# cam_cross_link.net
KiCad netlist of a schematic drawn in Altium Designer
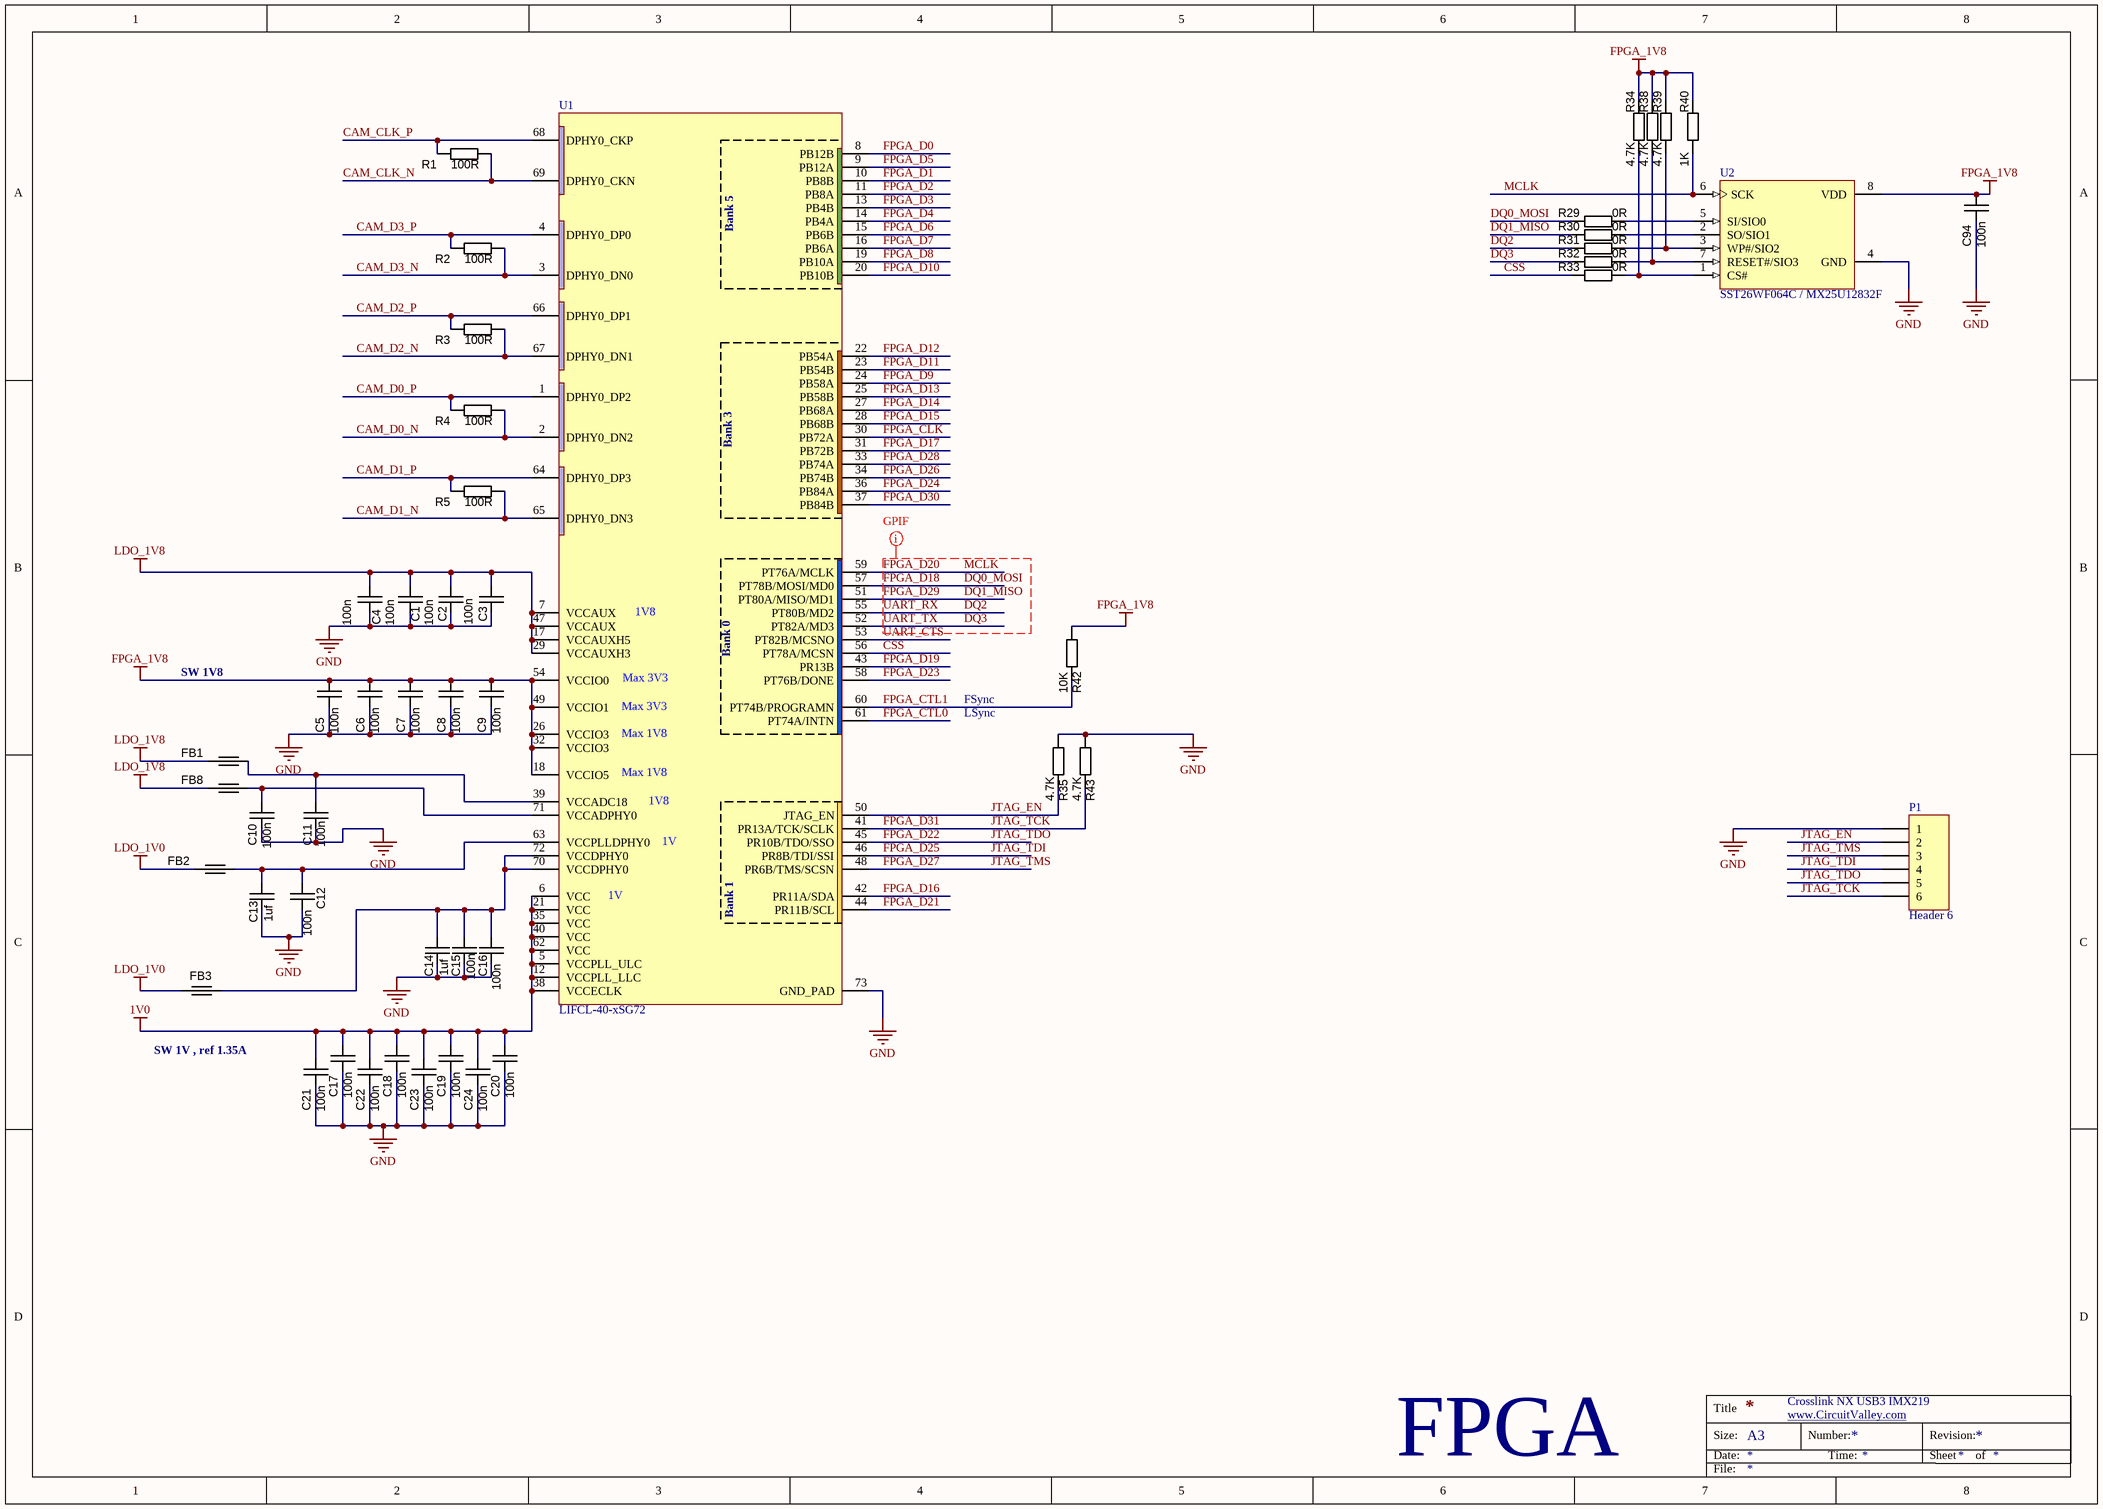
[diagram p0: cam_cross_link.SchDoc]

(export (version "E")
  (design (tool "Eeschema 10.0.6"))
  (components
    (comp (ref "C1")
      (value "100n")
      (footprint "CAPC1608N")
      (description "Capacitor SMD Cer 10pF 5% 50V NP0 0603")
      (fields (field (name "TOLERANCE") "±5%") (field (name "PART") "C0603X104K5RAC"))
      (libsource (lib "PBL - Capacitors") (part "CAPC_10p_0603_NP0_1%_50V"))
    )
    (comp (ref "C2")
      (value "100n")
      (footprint "CAPC1608N")
      (description "Capacitor SMD Cer 10pF 5% 50V NP0 0603")
      (fields (field (name "TOLERANCE") "±5%") (field (name "PART") "C0603X104K5RAC"))
      (libsource (lib "PBL - Capacitors") (part "CAPC_10p_0603_NP0_1%_50V"))
    )
    (comp (ref "C3")
      (value "100n")
      (footprint "CAPC1608N")
      (description "Capacitor SMD Cer 10pF 5% 50V NP0 0603")
      (fields (field (name "TOLERANCE") "±5%") (field (name "PART") "C0603X104K5RAC"))
      (libsource (lib "PBL - Capacitors") (part "CAPC_10p_0603_NP0_1%_50V"))
    )
    (comp (ref "C4")
      (value "100n")
      (footprint "CAPC1608N")
      (description "Capacitor SMD Cer 10pF 5% 50V NP0 0603")
      (fields (field (name "TOLERANCE") "±5%") (field (name "PART") "C0603X104K5RAC"))
      (libsource (lib "PBL - Capacitors") (part "CAPC_10p_0603_NP0_1%_50V"))
    )
    (comp (ref "C5")
      (value "100n")
      (footprint "CAPC1608N")
      (description "Capacitor SMD Cer 10pF 5% 50V NP0 0603")
      (fields (field (name "TOLERANCE") "±5%") (field (name "PART") "C0603X104K5RAC"))
      (libsource (lib "PBL - Capacitors") (part "CAPC_10p_0603_NP0_1%_50V"))
    )
    (comp (ref "C6")
      (value "100n")
      (footprint "CAPC1608N")
      (description "Capacitor SMD Cer 10pF 5% 50V NP0 0603")
      (fields (field (name "TOLERANCE") "±5%") (field (name "PART") "C0603X104K5RAC"))
      (libsource (lib "PBL - Capacitors") (part "CAPC_10p_0603_NP0_1%_50V"))
    )
    (comp (ref "C7")
      (value "100n")
      (footprint "CAPC1608N")
      (description "Capacitor SMD Cer 10pF 5% 50V NP0 0603")
      (fields (field (name "TOLERANCE") "±5%") (field (name "PART") "C0603X104K5RAC"))
      (libsource (lib "PBL - Capacitors") (part "CAPC_10p_0603_NP0_1%_50V"))
    )
    (comp (ref "C8")
      (value "100n")
      (footprint "CAPC1608N")
      (description "Capacitor SMD Cer 10pF 5% 50V NP0 0603")
      (fields (field (name "TOLERANCE") "±5%") (field (name "PART") "C0603X104K5RAC"))
      (libsource (lib "PBL - Capacitors") (part "CAPC_10p_0603_NP0_1%_50V"))
    )
    (comp (ref "C9")
      (value "100n")
      (footprint "CAPC1608N")
      (description "Capacitor SMD Cer 10pF 5% 50V NP0 0603")
      (fields (field (name "TOLERANCE") "±5%") (field (name "PART") "C0603X104K5RAC"))
      (libsource (lib "PBL - Capacitors") (part "CAPC_10p_0603_NP0_1%_50V"))
    )
    (comp (ref "C10")
      (value "100n")
      (footprint "CAPC1608N")
      (description "Capacitor SMD Cer 10pF 5% 50V NP0 0603")
      (fields (field (name "TOLERANCE") "±5%") (field (name "PART") "C0603X104K5RAC"))
      (libsource (lib "PBL - Capacitors") (part "CAPC_10p_0603_NP0_1%_50V"))
    )
    (comp (ref "C11")
      (value "100n")
      (footprint "CAPC1608N")
      (description "Capacitor SMD Cer 10pF 5% 50V NP0 0603")
      (fields (field (name "TOLERANCE") "±5%") (field (name "PART") "C0603X104K5RAC"))
      (libsource (lib "PBL - Capacitors") (part "CAPC_10p_0603_NP0_1%_50V"))
    )
    (comp (ref "C12")
      (value "100n")
      (footprint "CAPC1608N")
      (description "Capacitor SMD Cer 10pF 5% 50V NP0 0603")
      (fields (field (name "TOLERANCE") "±5%") (field (name "PART") "C0603X104K5RAC"))
      (libsource (lib "PBL - Capacitors") (part "CAPC_10p_0603_NP0_1%_50V"))
    )
    (comp (ref "C13")
      (value "1uf")
      (footprint "CAPC1608N")
      (description "Capacitor SMD Cer 10pF 5% 50V NP0 0603")
      (fields (field (name "TOLERANCE") "±5%") (field (name "PART") "C0603X104K5RAC"))
      (libsource (lib "PBL - Capacitors") (part "CAPC_10p_0603_NP0_1%_50V"))
    )
    (comp (ref "C14")
      (value "1uf")
      (footprint "CAPC1608N")
      (description "Capacitor SMD Cer 10pF 5% 50V NP0 0603")
      (fields (field (name "TOLERANCE") "±5%") (field (name "PART") "C0603X104K5RAC"))
      (libsource (lib "PBL - Capacitors") (part "CAPC_10p_0603_NP0_1%_50V"))
    )
    (comp (ref "C15")
      (value "100n")
      (footprint "CAPC1608N")
      (description "Capacitor SMD Cer 10pF 5% 50V NP0 0603")
      (fields (field (name "TOLERANCE") "±5%") (field (name "PART") "C0603X104K5RAC"))
      (libsource (lib "PBL - Capacitors") (part "CAPC_10p_0603_NP0_1%_50V"))
    )
    (comp (ref "C16")
      (value "100n")
      (footprint "CAPC1608N")
      (description "Capacitor SMD Cer 10pF 5% 50V NP0 0603")
      (fields (field (name "TOLERANCE") "±5%") (field (name "PART") "C0603X104K5RAC"))
      (libsource (lib "PBL - Capacitors") (part "CAPC_10p_0603_NP0_1%_50V"))
    )
    (comp (ref "C17")
      (value "100n")
      (footprint "CAPC1608N")
      (description "Capacitor SMD Cer 10pF 5% 50V NP0 0603")
      (fields (field (name "TOLERANCE") "±5%") (field (name "PART") "C0603X104K5RAC"))
      (libsource (lib "PBL - Capacitors") (part "CAPC_10p_0603_NP0_1%_50V"))
    )
    (comp (ref "C18")
      (value "100n")
      (footprint "CAPC1608N")
      (description "Capacitor SMD Cer 10pF 5% 50V NP0 0603")
      (fields (field (name "TOLERANCE") "±5%") (field (name "PART") "C0603X104K5RAC"))
      (libsource (lib "PBL - Capacitors") (part "CAPC_10p_0603_NP0_1%_50V"))
    )
    (comp (ref "C19")
      (value "100n")
      (footprint "CAPC1608N")
      (description "Capacitor SMD Cer 10pF 5% 50V NP0 0603")
      (fields (field (name "TOLERANCE") "±5%") (field (name "PART") "C0603X104K5RAC"))
      (libsource (lib "PBL - Capacitors") (part "CAPC_10p_0603_NP0_1%_50V"))
    )
    (comp (ref "C20")
      (value "100n")
      (footprint "CAPC1608N")
      (description "Capacitor SMD Cer 10pF 5% 50V NP0 0603")
      (fields (field (name "TOLERANCE") "±5%") (field (name "PART") "C0603X104K5RAC"))
      (libsource (lib "PBL - Capacitors") (part "CAPC_10p_0603_NP0_1%_50V"))
    )
    (comp (ref "C21")
      (value "100n")
      (footprint "CAPC1608N")
      (description "Capacitor SMD Cer 10pF 5% 50V NP0 0603")
      (fields (field (name "TOLERANCE") "±5%") (field (name "PART") "C0603X104K5RAC"))
      (libsource (lib "PBL - Capacitors") (part "CAPC_10p_0603_NP0_1%_50V"))
    )
    (comp (ref "C22")
      (value "100n")
      (footprint "CAPC1608N")
      (description "Capacitor SMD Cer 10pF 5% 50V NP0 0603")
      (fields (field (name "TOLERANCE") "±5%") (field (name "PART") "C0603X104K5RAC"))
      (libsource (lib "PBL - Capacitors") (part "CAPC_10p_0603_NP0_1%_50V"))
    )
    (comp (ref "C23")
      (value "100n")
      (footprint "CAPC1608N")
      (description "Capacitor SMD Cer 10pF 5% 50V NP0 0603")
      (fields (field (name "TOLERANCE") "±5%") (field (name "PART") "C0603X104K5RAC"))
      (libsource (lib "PBL - Capacitors") (part "CAPC_10p_0603_NP0_1%_50V"))
    )
    (comp (ref "C24")
      (value "100n")
      (footprint "CAPC1608N")
      (description "Capacitor SMD Cer 10pF 5% 50V NP0 0603")
      (fields (field (name "TOLERANCE") "±5%") (field (name "PART") "C0603X104K5RAC"))
      (libsource (lib "PBL - Capacitors") (part "CAPC_10p_0603_NP0_1%_50V"))
    )
    (comp (ref "C94")
      (value "100n")
      (footprint "CAPC1608N")
      (description "Capacitor SMD Cer 10pF 5% 50V NP0 0603")
      (fields (field (name "TOLERANCE") "±5%") (field (name "PART") "C0603X104K5RAC"))
      (libsource (lib "PBL - Capacitors") (part "CAPC_10p_0603_NP0_1%_50V"))
    )
    (comp (ref "FB1")
      (value "~")
      (footprint "FBC2012N")
      (description "Ferrite bead 2.2K Ohm at 100 MHz 200mA 0805 SMD")
      (libsource (lib "PBL - Inductors") (part "FERRITE_0805"))
    )
    (comp (ref "FB2")
      (value "~")
      (footprint "FBC2012N")
      (description "Ferrite bead 2.2K Ohm at 100 MHz 200mA 0805 SMD")
      (libsource (lib "PBL - Inductors") (part "FERRITE_0805"))
    )
    (comp (ref "FB3")
      (value "~")
      (footprint "FBC2012N")
      (description "Ferrite bead 2.2K Ohm at 100 MHz 200mA 0805 SMD")
      (libsource (lib "PBL - Inductors") (part "FERRITE_0805"))
    )
    (comp (ref "FB8")
      (value "~")
      (footprint "FBC2012N")
      (description "Ferrite bead 2.2K Ohm at 100 MHz 200mA 0805 SMD")
      (libsource (lib "PBL - Inductors") (part "FERRITE_0805"))
    )
    (comp (ref "P1")
      (value "Header 6")
      (footprint "SMD_Solder_points_1.27")
      (description "Header, 6-Pin")
      (fields (field (name "PUBLISHER") "Altium Limited"))
      (libsource (lib "Miscellaneous Connectors") (part "Header 6"))
    )
    (comp (ref "R1")
      (value "100R")
      (footprint "RESC1005N")
      (description "Resistor SMD chip 1M Ohm 0.063W 5% 0402")
      (fields (field (name "TOLERANCE") "±5%") (field (name "Comment") "Thick Film"))
      (libsource (lib "PBL - Resistors") (part "RES_1M_0402_5%"))
    )
    (comp (ref "R2")
      (value "100R")
      (footprint "RESC1005N")
      (description "Resistor SMD chip 1M Ohm 0.063W 5% 0402")
      (fields (field (name "TOLERANCE") "±5%") (field (name "Comment") "Thick Film"))
      (libsource (lib "PBL - Resistors") (part "RES_1M_0402_5%"))
    )
    (comp (ref "R3")
      (value "100R")
      (footprint "RESC1005N")
      (description "Resistor SMD chip 1M Ohm 0.063W 5% 0402")
      (fields (field (name "TOLERANCE") "±5%") (field (name "Comment") "Thick Film"))
      (libsource (lib "PBL - Resistors") (part "RES_1M_0402_5%"))
    )
    (comp (ref "R4")
      (value "100R")
      (footprint "RESC1005N")
      (description "Resistor SMD chip 1M Ohm 0.063W 5% 0402")
      (fields (field (name "TOLERANCE") "±5%") (field (name "Comment") "Thick Film"))
      (libsource (lib "PBL - Resistors") (part "RES_1M_0402_5%"))
    )
    (comp (ref "R5")
      (value "100R")
      (footprint "RESC1005N")
      (description "Resistor SMD chip 1M Ohm 0.063W 5% 0402")
      (fields (field (name "TOLERANCE") "±5%") (field (name "Comment") "Thick Film"))
      (libsource (lib "PBL - Resistors") (part "RES_1M_0402_5%"))
    )
    (comp (ref "R29")
      (value "0R")
      (footprint "RESC1608N_ZERO")
      (description "Resistor SMD chip 0.0 Ohm 0.1W 0603")
      (fields (field (name "TOLERANCE") "±5%") (field (name "Comment") "Thick Film"))
      (libsource (lib "") (part "RES_0R_0603_1"))
    )
    (comp (ref "R30")
      (value "0R")
      (footprint "RESC1608N_ZERO")
      (description "Resistor SMD chip 0.0 Ohm 0.1W 0603")
      (fields (field (name "TOLERANCE") "±5%") (field (name "Comment") "Thick Film"))
      (libsource (lib "") (part "RES_0R_0603_1"))
    )
    (comp (ref "R31")
      (value "0R")
      (footprint "RESC1608N_ZERO")
      (description "Resistor SMD chip 0.0 Ohm 0.1W 0603")
      (fields (field (name "TOLERANCE") "±5%") (field (name "Comment") "Thick Film"))
      (libsource (lib "") (part "RES_0R_0603_1"))
    )
    (comp (ref "R32")
      (value "0R")
      (footprint "RESC1608N_ZERO")
      (description "Resistor SMD chip 0.0 Ohm 0.1W 0603")
      (fields (field (name "TOLERANCE") "±5%") (field (name "Comment") "Thick Film"))
      (libsource (lib "") (part "RES_0R_0603_1"))
    )
    (comp (ref "R33")
      (value "0R")
      (footprint "RESC1608N_ZERO")
      (description "Resistor SMD chip 0.0 Ohm 0.1W 0603")
      (fields (field (name "TOLERANCE") "±5%") (field (name "Comment") "Thick Film"))
      (libsource (lib "") (part "RES_0R_0603_1"))
    )
    (comp (ref "R34")
      (value "4.7K")
      (footprint "RESC1608N_ZERO")
      (description "Resistor SMD chip 0.0 Ohm 0.1W 0603")
      (fields (field (name "TOLERANCE") "±5%") (field (name "Comment") "Thick Film"))
      (libsource (lib "PBL - Resistors") (part "RES_0R_0603"))
    )
    (comp (ref "R35")
      (value "4.7K")
      (footprint "RESC1608N_ZERO")
      (description "Resistor SMD chip 0.0 Ohm 0.1W 0603")
      (fields (field (name "TOLERANCE") "±5%") (field (name "Comment") "Thick Film"))
      (libsource (lib "PBL - Resistors") (part "RES_0R_0603"))
    )
    (comp (ref "R38")
      (value "4.7K")
      (footprint "RESC1608N_ZERO")
      (description "Resistor SMD chip 0.0 Ohm 0.1W 0603")
      (fields (field (name "TOLERANCE") "±5%") (field (name "Comment") "Thick Film"))
      (libsource (lib "PBL - Resistors") (part "RES_0R_0603"))
    )
    (comp (ref "R39")
      (value "4.7K")
      (footprint "RESC1608N_ZERO")
      (description "Resistor SMD chip 0.0 Ohm 0.1W 0603")
      (fields (field (name "TOLERANCE") "±5%") (field (name "Comment") "Thick Film"))
      (libsource (lib "PBL - Resistors") (part "RES_0R_0603"))
    )
    (comp (ref "R40")
      (value "1K")
      (footprint "RESC1608N_ZERO")
      (description "Resistor SMD chip 0.0 Ohm 0.1W 0603")
      (fields (field (name "TOLERANCE") "±5%") (field (name "Comment") "Thick Film"))
      (libsource (lib "PBL - Resistors") (part "RES_0R_0603"))
    )
    (comp (ref "R42")
      (value "10K")
      (footprint "RESC1608N_ZERO")
      (description "Resistor SMD chip 0.0 Ohm 0.1W 0603")
      (fields (field (name "TOLERANCE") "±5%") (field (name "Comment") "Thick Film"))
      (libsource (lib "PBL - Resistors") (part "RES_0R_0603"))
    )
    (comp (ref "R43")
      (value "4.7K")
      (footprint "RESC1608N_ZERO")
      (description "Resistor SMD chip 0.0 Ohm 0.1W 0603")
      (fields (field (name "TOLERANCE") "±5%") (field (name "Comment") "Thick Film"))
      (libsource (lib "PBL - Resistors") (part "RES_0R_0603"))
    )
    (comp (ref "U1")
      (value "LIFCL-40-xSG72")
      (footprint "QFN72_NX")
      (description "QFN 72 LIFCL")
      (libsource (lib "lattice_fpga") (part "LIFCL-40-xSG72"))
    )
    (comp (ref "U2")
      (value "SST26WF064C / MX25U12832F")
      (footprint "SOP8")
      (description "Flash 128Mbit for Lattice FPGA")
      (libsource (lib "cvlib") (part "MX25L12833F"))
    )
  )
  (nets
    (net (code "1") (name "/CAM_CLK_N") (class "Default")
      (node (ref "R1") (pin "1") (pinfunction "1_1") (pintype "passive"))
      (node (ref "U1") (pin "69") (pinfunction "DPHY0_CKN_69") (pintype "passive"))
    )
    (net (code "2") (name "/CAM_CLK_P") (class "Default")
      (node (ref "R1") (pin "2") (pinfunction "2_2") (pintype "passive"))
      (node (ref "U1") (pin "68") (pinfunction "DPHY0_CKP_68") (pintype "passive"))
    )
    (net (code "3") (name "/CAM_D0_N") (class "Default")
      (node (ref "R4") (pin "1") (pinfunction "1_1") (pintype "passive"))
      (node (ref "U1") (pin "2") (pinfunction "DPHY0_DN2_2") (pintype "passive"))
    )
    (net (code "4") (name "/CAM_D0_P") (class "Default")
      (node (ref "R4") (pin "2") (pinfunction "2_2") (pintype "passive"))
      (node (ref "U1") (pin "1") (pinfunction "DPHY0_DP2_1") (pintype "passive"))
    )
    (net (code "5") (name "/CAM_D1_N") (class "Default")
      (node (ref "R5") (pin "1") (pinfunction "1_1") (pintype "passive"))
      (node (ref "U1") (pin "65") (pinfunction "DPHY0_DN3_65") (pintype "passive"))
    )
    (net (code "6") (name "/CAM_D1_P") (class "Default")
      (node (ref "R5") (pin "2") (pinfunction "2_2") (pintype "passive"))
      (node (ref "U1") (pin "64") (pinfunction "DPHY0_DP3_64") (pintype "passive"))
    )
    (net (code "7") (name "/CAM_D2_N") (class "Default")
      (node (ref "R3") (pin "1") (pinfunction "1_1") (pintype "passive"))
      (node (ref "U1") (pin "67") (pinfunction "DPHY0_DN1_67") (pintype "passive"))
    )
    (net (code "8") (name "/CAM_D2_P") (class "Default")
      (node (ref "R3") (pin "2") (pinfunction "2_2") (pintype "passive"))
      (node (ref "U1") (pin "66") (pinfunction "DPHY0_DP1_66") (pintype "passive"))
    )
    (net (code "9") (name "/CAM_D3_N") (class "Default")
      (node (ref "R2") (pin "1") (pinfunction "1_1") (pintype "passive"))
      (node (ref "U1") (pin "3") (pinfunction "DPHY0_DN0_3") (pintype "passive"))
    )
    (net (code "10") (name "/CAM_D3_P") (class "Default")
      (node (ref "R2") (pin "2") (pinfunction "2_2") (pintype "passive"))
      (node (ref "U1") (pin "4") (pinfunction "DPHY0_DP0_4") (pintype "passive"))
    )
    (net (code "11") (name "/CSS") (class "Default")
      (node (ref "R33") (pin "2") (pinfunction "2_2") (pintype "passive"))
      (node (ref "U1") (pin "56") (pinfunction "PT78A/MCSN_56") (pintype "passive"))
    )
    (net (code "12") (name "/DQ0_MOSI") (class "Default")
      (node (ref "R29") (pin "2") (pinfunction "2_2") (pintype "passive"))
      (node (ref "U1") (pin "57") (pinfunction "PT78B/MOSI/MD0_57") (pintype "passive"))
    )
    (net (code "13") (name "/DQ1_MISO") (class "Default")
      (node (ref "R30") (pin "2") (pinfunction "2_2") (pintype "passive"))
      (node (ref "U1") (pin "51") (pinfunction "PT80A/MISO/MD1_51") (pintype "passive"))
    )
    (net (code "14") (name "/DQ2") (class "Default")
      (node (ref "R31") (pin "2") (pinfunction "2_2") (pintype "passive"))
      (node (ref "U1") (pin "55") (pinfunction "PT80B/MD2_55") (pintype "passive"))
    )
    (net (code "15") (name "/DQ3") (class "Default")
      (node (ref "R32") (pin "2") (pinfunction "2_2") (pintype "passive"))
      (node (ref "U1") (pin "52") (pinfunction "PT82A/MD3_52") (pintype "passive"))
    )
    (net (code "16") (name "/FPGA_CLK") (class "Default")
      (node (ref "U1") (pin "30") (pinfunction "PB72A_30") (pintype "passive"))
    )
    (net (code "17") (name "/FPGA_CTL0") (class "Default")
      (node (ref "U1") (pin "61") (pinfunction "PT74A/INTN_61") (pintype "passive"))
    )
    (net (code "18") (name "/FPGA_CTL1") (class "Default")
      (node (ref "R42") (pin "2") (pinfunction "2_2") (pintype "passive"))
      (node (ref "U1") (pin "60") (pinfunction "PT74B/PROGRAMN_60") (pintype "passive"))
    )
    (net (code "19") (name "/FPGA_D0") (class "Default")
      (node (ref "U1") (pin "8") (pinfunction "PB12B_8") (pintype "passive"))
    )
    (net (code "20") (name "/FPGA_D1") (class "Default")
      (node (ref "U1") (pin "10") (pinfunction "PB8B_10") (pintype "passive"))
    )
    (net (code "21") (name "/FPGA_D2") (class "Default")
      (node (ref "U1") (pin "11") (pinfunction "PB8A_11") (pintype "passive"))
    )
    (net (code "22") (name "/FPGA_D3") (class "Default")
      (node (ref "U1") (pin "13") (pinfunction "PB4B_13") (pintype "passive"))
    )
    (net (code "23") (name "/FPGA_D4") (class "Default")
      (node (ref "U1") (pin "14") (pinfunction "PB4A_14") (pintype "passive"))
    )
    (net (code "24") (name "/FPGA_D5") (class "Default")
      (node (ref "U1") (pin "9") (pinfunction "PB12A_9") (pintype "passive"))
    )
    (net (code "25") (name "/FPGA_D6") (class "Default")
      (node (ref "U1") (pin "15") (pinfunction "PB6B_15") (pintype "passive"))
    )
    (net (code "26") (name "/FPGA_D7") (class "Default")
      (node (ref "U1") (pin "16") (pinfunction "PB6A_16") (pintype "passive"))
    )
    (net (code "27") (name "/FPGA_D8") (class "Default")
      (node (ref "U1") (pin "19") (pinfunction "PB10A_19") (pintype "passive"))
    )
    (net (code "28") (name "/FPGA_D9") (class "Default")
      (node (ref "U1") (pin "24") (pinfunction "PB58A_24") (pintype "passive"))
    )
    (net (code "29") (name "/FPGA_D10") (class "Default")
      (node (ref "U1") (pin "20") (pinfunction "PB10B_20") (pintype "passive"))
    )
    (net (code "30") (name "/FPGA_D11") (class "Default")
      (node (ref "U1") (pin "23") (pinfunction "PB54B_23") (pintype "passive"))
    )
    (net (code "31") (name "/FPGA_D12") (class "Default")
      (node (ref "U1") (pin "22") (pinfunction "PB54A_22") (pintype "passive"))
    )
    (net (code "32") (name "/FPGA_D13") (class "Default")
      (node (ref "U1") (pin "25") (pinfunction "PB58B_25") (pintype "passive"))
    )
    (net (code "33") (name "/FPGA_D14") (class "Default")
      (node (ref "U1") (pin "27") (pinfunction "PB68A_27") (pintype "passive"))
    )
    (net (code "34") (name "/FPGA_D15") (class "Default")
      (node (ref "U1") (pin "28") (pinfunction "PB68B_28") (pintype "passive"))
    )
    (net (code "35") (name "/FPGA_D16") (class "Default")
      (node (ref "U1") (pin "42") (pinfunction "PR11A/SDA_42") (pintype "passive"))
    )
    (net (code "36") (name "/FPGA_D17") (class "Default")
      (node (ref "U1") (pin "31") (pinfunction "PB72B_31") (pintype "passive"))
    )
    (net (code "37") (name "/FPGA_D19") (class "Default")
      (node (ref "U1") (pin "43") (pinfunction "PR13B_43") (pintype "passive"))
    )
    (net (code "38") (name "/FPGA_D20") (class "Default")
      (node (ref "R40") (pin "2") (pinfunction "2_2") (pintype "passive"))
      (node (ref "U1") (pin "59") (pinfunction "PT76A/MCLK_59") (pintype "passive"))
      (node (ref "U2") (pin "6") (pinfunction "SCK_6") (pintype "input"))
    )
    (net (code "39") (name "/FPGA_D21") (class "Default")
      (node (ref "U1") (pin "44") (pinfunction "PR11B/SCL_44") (pintype "passive"))
    )
    (net (code "40") (name "/FPGA_D22") (class "Default")
      (node (ref "P1") (pin "5") (pinfunction "5_5") (pintype "passive"))
      (node (ref "U1") (pin "45") (pinfunction "PR10B/TDO/SSO_45") (pintype "passive"))
    )
    (net (code "41") (name "/FPGA_D23") (class "Default")
      (node (ref "U1") (pin "58") (pinfunction "PT76B/DONE_58") (pintype "passive"))
    )
    (net (code "42") (name "/FPGA_D24") (class "Default")
      (node (ref "U1") (pin "36") (pinfunction "PB84A_36") (pintype "passive"))
    )
    (net (code "43") (name "/FPGA_D25") (class "Default")
      (node (ref "P1") (pin "4") (pinfunction "4_4") (pintype "passive"))
      (node (ref "U1") (pin "46") (pinfunction "PR8B/TDI/SSI_46") (pintype "passive"))
    )
    (net (code "44") (name "/FPGA_D26") (class "Default")
      (node (ref "U1") (pin "34") (pinfunction "PB74B_34") (pintype "passive"))
    )
    (net (code "45") (name "/FPGA_D27") (class "Default")
      (node (ref "P1") (pin "3") (pinfunction "3_3") (pintype "passive"))
      (node (ref "U1") (pin "48") (pinfunction "PR6B/TMS/SCSN_48") (pintype "passive"))
    )
    (net (code "46") (name "/FPGA_D28") (class "Default")
      (node (ref "U1") (pin "33") (pinfunction "PB74A_33") (pintype "passive"))
    )
    (net (code "47") (name "/FPGA_D30") (class "Default")
      (node (ref "U1") (pin "37") (pinfunction "PB84B_37") (pintype "passive"))
    )
    (net (code "48") (name "/FPGA_D31") (class "Default")
      (node (ref "P1") (pin "6") (pinfunction "6_6") (pintype "passive"))
      (node (ref "R43") (pin "2") (pinfunction "2_2") (pintype "passive"))
      (node (ref "U1") (pin "41") (pinfunction "PR13A/TCK/SCLK_41") (pintype "passive"))
    )
    (net (code "49") (name "/JTAG_EN") (class "Default")
      (node (ref "P1") (pin "2") (pinfunction "2_2") (pintype "passive"))
      (node (ref "R35") (pin "2") (pinfunction "2_2") (pintype "passive"))
      (node (ref "U1") (pin "50") (pinfunction "JTAG_EN_50") (pintype "passive"))
    )
    (net (code "50") (name "/UART_CTS") (class "Default")
      (node (ref "U1") (pin "53") (pinfunction "PT82B/MCSNO_53") (pintype "passive"))
    )
    (net (code "51") (name "1V0") (class "Default")
      (node (ref "C17") (pin "2") (pintype "passive"))
      (node (ref "C18") (pin "2") (pintype "passive"))
      (node (ref "C19") (pin "2") (pintype "passive"))
      (node (ref "C20") (pin "2") (pintype "passive"))
      (node (ref "C21") (pin "2") (pintype "passive"))
      (node (ref "C22") (pin "2") (pintype "passive"))
      (node (ref "C23") (pin "2") (pintype "passive"))
      (node (ref "C24") (pin "2") (pintype "passive"))
      (node (ref "U1") (pin "12") (pinfunction "VCCPLL_LLC_12") (pintype "power_in"))
      (node (ref "U1") (pin "21") (pinfunction "VCC_21") (pintype "power_in"))
      (node (ref "U1") (pin "35") (pinfunction "VCC_35") (pintype "power_in"))
      (node (ref "U1") (pin "38") (pinfunction "VCCECLK_38") (pintype "power_in"))
      (node (ref "U1") (pin "40") (pinfunction "VCC_40") (pintype "power_in"))
      (node (ref "U1") (pin "5") (pinfunction "VCCPLL_ULC_5") (pintype "power_in"))
      (node (ref "U1") (pin "6") (pinfunction "VCC_6") (pintype "power_in"))
      (node (ref "U1") (pin "62") (pinfunction "VCC_62") (pintype "power_in"))
    )
    (net (code "52") (name "FPGA_1V8") (class "Default")
      (node (ref "C5") (pin "2") (pintype "passive"))
      (node (ref "C6") (pin "2") (pintype "passive"))
      (node (ref "C7") (pin "2") (pintype "passive"))
      (node (ref "C8") (pin "2") (pintype "passive"))
      (node (ref "C9") (pin "2") (pintype "passive"))
      (node (ref "C94") (pin "2") (pintype "passive"))
      (node (ref "R34") (pin "1") (pinfunction "1_1") (pintype "passive"))
      (node (ref "R38") (pin "1") (pinfunction "1_1") (pintype "passive"))
      (node (ref "R39") (pin "1") (pinfunction "1_1") (pintype "passive"))
      (node (ref "R40") (pin "1") (pinfunction "1_1") (pintype "passive"))
      (node (ref "R42") (pin "1") (pinfunction "1_1") (pintype "passive"))
      (node (ref "U1") (pin "18") (pinfunction "VCCIO5_18") (pintype "power_in"))
      (node (ref "U1") (pin "26") (pinfunction "VCCIO3_26") (pintype "power_in"))
      (node (ref "U1") (pin "32") (pinfunction "VCCIO3_32") (pintype "power_in"))
      (node (ref "U1") (pin "49") (pinfunction "VCCIO1_49") (pintype "power_in"))
      (node (ref "U1") (pin "54") (pinfunction "VCCIO0_54") (pintype "power_in"))
      (node (ref "U2") (pin "8") (pinfunction "VDD_8") (pintype "power_in"))
    )
    (net (code "53") (name "GND") (class "Default")
      (node (ref "C1") (pin "1") (pintype "passive"))
      (node (ref "C10") (pin "1") (pintype "passive"))
      (node (ref "C11") (pin "1") (pintype "passive"))
      (node (ref "C12") (pin "2") (pintype "passive"))
      (node (ref "C13") (pin "1") (pintype "passive"))
      (node (ref "C14") (pin "1") (pintype "passive"))
      (node (ref "C15") (pin "1") (pintype "passive"))
      (node (ref "C16") (pin "1") (pintype "passive"))
      (node (ref "C17") (pin "1") (pintype "passive"))
      (node (ref "C18") (pin "1") (pintype "passive"))
      (node (ref "C19") (pin "1") (pintype "passive"))
      (node (ref "C2") (pin "1") (pintype "passive"))
      (node (ref "C20") (pin "1") (pintype "passive"))
      (node (ref "C21") (pin "1") (pintype "passive"))
      (node (ref "C22") (pin "1") (pintype "passive"))
      (node (ref "C23") (pin "1") (pintype "passive"))
      (node (ref "C24") (pin "1") (pintype "passive"))
      (node (ref "C3") (pin "1") (pintype "passive"))
      (node (ref "C4") (pin "1") (pintype "passive"))
      (node (ref "C5") (pin "1") (pintype "passive"))
      (node (ref "C6") (pin "1") (pintype "passive"))
      (node (ref "C7") (pin "1") (pintype "passive"))
      (node (ref "C8") (pin "1") (pintype "passive"))
      (node (ref "C9") (pin "1") (pintype "passive"))
      (node (ref "C94") (pin "1") (pintype "passive"))
      (node (ref "P1") (pin "1") (pinfunction "1_1") (pintype "passive"))
      (node (ref "R35") (pin "1") (pinfunction "1_1") (pintype "passive"))
      (node (ref "R43") (pin "1") (pinfunction "1_1") (pintype "passive"))
      (node (ref "U1") (pin "73") (pinfunction "GND_PAD_73") (pintype "power_in"))
      (node (ref "U2") (pin "4") (pinfunction "GND_4") (pintype "power_in"))
    )
    (net (code "54") (name "LDO_1V0") (class "Default")
      (node (ref "FB2") (pin "1") (pinfunction "1_1") (pintype "passive"))
      (node (ref "FB3") (pin "1") (pinfunction "1_1") (pintype "passive"))
    )
    (net (code "55") (name "LDO_1V8") (class "Default")
      (node (ref "C1") (pin "2") (pintype "passive"))
      (node (ref "C2") (pin "2") (pintype "passive"))
      (node (ref "C3") (pin "2") (pintype "passive"))
      (node (ref "C4") (pin "2") (pintype "passive"))
      (node (ref "FB1") (pin "1") (pinfunction "1_1") (pintype "passive"))
      (node (ref "FB8") (pin "1") (pinfunction "1_1") (pintype "passive"))
      (node (ref "U1") (pin "17") (pinfunction "VCCAUXH5_17") (pintype "power_in"))
      (node (ref "U1") (pin "29") (pinfunction "VCCAUXH3_29") (pintype "passive"))
      (node (ref "U1") (pin "47") (pinfunction "VCCAUX_47") (pintype "power_in"))
      (node (ref "U1") (pin "7") (pinfunction "VCCAUX_7") (pintype "power_in"))
    )
    (net (code "56") (name "Net-(C14-Pad2)") (class "Default")
      (node (ref "C14") (pin "2") (pintype "passive"))
      (node (ref "C15") (pin "2") (pintype "passive"))
      (node (ref "C16") (pin "2") (pintype "passive"))
      (node (ref "FB3") (pin "2") (pinfunction "2_2") (pintype "passive"))
      (node (ref "U1") (pin "70") (pinfunction "VCCDPHY0_70") (pintype "passive"))
      (node (ref "U1") (pin "72") (pinfunction "VCCDPHY0_72") (pintype "passive"))
    )
    (net (code "57") (name "Net-(U1-VCCADC18)") (class "Default")
      (node (ref "C11") (pin "2") (pintype "passive"))
      (node (ref "FB1") (pin "2") (pinfunction "2_2") (pintype "passive"))
      (node (ref "U1") (pin "39") (pinfunction "VCCADC18_39") (pintype "power_in"))
    )
    (net (code "58") (name "Net-(U1-VCCADPHY0)") (class "Default")
      (node (ref "C10") (pin "2") (pintype "passive"))
      (node (ref "FB8") (pin "2") (pinfunction "2_2") (pintype "passive"))
      (node (ref "U1") (pin "71") (pinfunction "VCCADPHY0_71") (pintype "passive"))
    )
    (net (code "59") (name "Net-(U1-VCCPLLDPHY0)") (class "Default")
      (node (ref "C12") (pin "1") (pintype "passive"))
      (node (ref "C13") (pin "2") (pintype "passive"))
      (node (ref "FB2") (pin "2") (pinfunction "2_2") (pintype "passive"))
      (node (ref "U1") (pin "63") (pinfunction "VCCPLLDPHY0_63") (pintype "power_in"))
    )
    (net (code "60") (name "Net-(U2-CS#)") (class "Default")
      (node (ref "R33") (pin "1") (pinfunction "1_1") (pintype "passive"))
      (node (ref "R34") (pin "2") (pinfunction "2_2") (pintype "passive"))
      (node (ref "U2") (pin "1") (pinfunction "CS#_1") (pintype "input"))
    )
    (net (code "61") (name "Net-(U2-RESET#{slash}SIO3)") (class "Default")
      (node (ref "R32") (pin "1") (pinfunction "1_1") (pintype "passive"))
      (node (ref "R38") (pin "2") (pinfunction "2_2") (pintype "passive"))
      (node (ref "U2") (pin "7") (pinfunction "RESET#/SIO3_7") (pintype "input"))
    )
    (net (code "62") (name "Net-(U2-SI{slash}SIO0)") (class "Default")
      (node (ref "R29") (pin "1") (pinfunction "1_1") (pintype "passive"))
      (node (ref "U2") (pin "5") (pinfunction "SI/SIO0_5") (pintype "input"))
    )
    (net (code "63") (name "Net-(U2-SO{slash}SIO1)") (class "Default")
      (node (ref "R30") (pin "1") (pinfunction "1_1") (pintype "passive"))
      (node (ref "U2") (pin "2") (pinfunction "SO/SIO1_2") (pintype "tri_state"))
    )
    (net (code "64") (name "Net-(U2-WP#{slash}SIO2)") (class "Default")
      (node (ref "R31") (pin "1") (pinfunction "1_1") (pintype "passive"))
      (node (ref "R39") (pin "2") (pinfunction "2_2") (pintype "passive"))
      (node (ref "U2") (pin "3") (pinfunction "WP#/SIO2_3") (pintype "input"))
    )
  )
)
